# c3.net
KiCad netlist of a schematic drawn in EAGLE
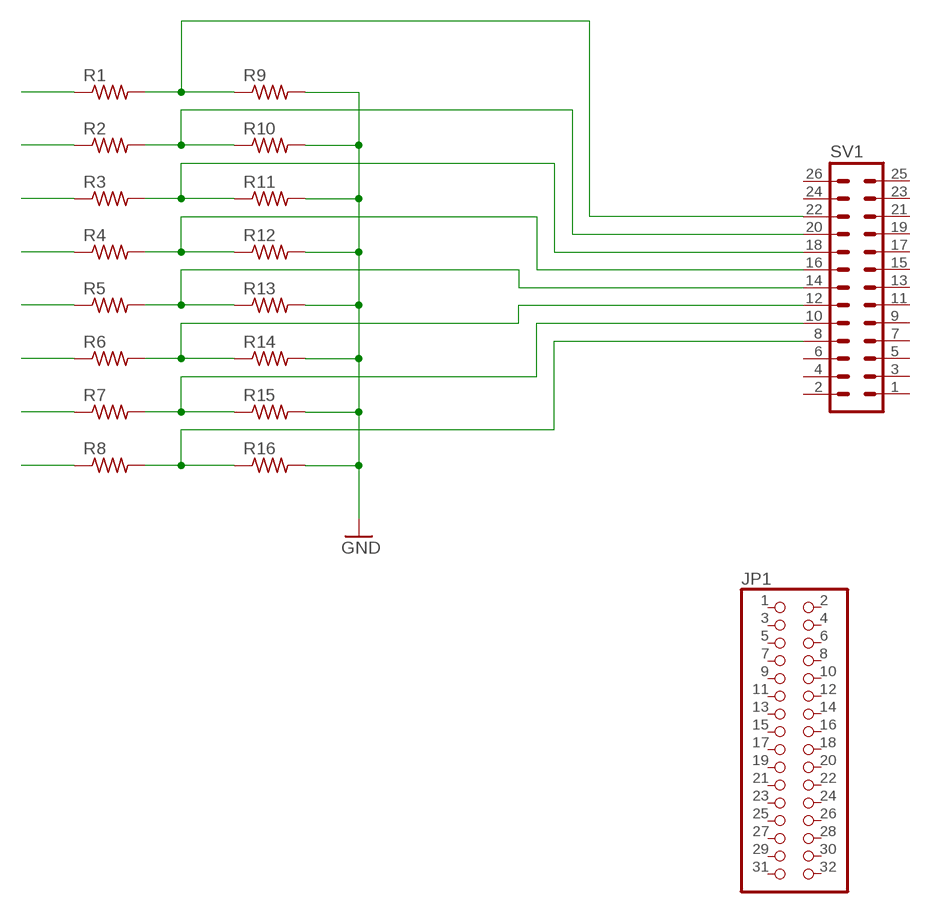
[diagram p0: schematic, sheet 1]

(export (version "E")
  (design (tool "Eeschema 10.0.6"))
  (components
    (comp (ref "JP1")
      (value "PINHD-2X16")
      (footprint "eagle-import:2X16")
      (libsource (lib "eagle-import") (part "PINHD-2X16"))
    )
    (comp (ref "R1")
      (value "R-US_0204/7")
      (footprint "eagle-import:0204_7")
      (libsource (lib "eagle-import") (part "R-US_0204/7"))
    )
    (comp (ref "R2")
      (value "R-US_0204/7")
      (footprint "eagle-import:0204_7")
      (libsource (lib "eagle-import") (part "R-US_0204/7"))
    )
    (comp (ref "R3")
      (value "R-US_0204/7")
      (footprint "eagle-import:0204_7")
      (libsource (lib "eagle-import") (part "R-US_0204/7"))
    )
    (comp (ref "R4")
      (value "R-US_0204/7")
      (footprint "eagle-import:0204_7")
      (libsource (lib "eagle-import") (part "R-US_0204/7"))
    )
    (comp (ref "R5")
      (value "R-US_0204/7")
      (footprint "eagle-import:0204_7")
      (libsource (lib "eagle-import") (part "R-US_0204/7"))
    )
    (comp (ref "R6")
      (value "R-US_0204/7")
      (footprint "eagle-import:0204_7")
      (libsource (lib "eagle-import") (part "R-US_0204/7"))
    )
    (comp (ref "R7")
      (value "R-US_0204/7")
      (footprint "eagle-import:0204_7")
      (libsource (lib "eagle-import") (part "R-US_0204/7"))
    )
    (comp (ref "R8")
      (value "R-US_0204/7")
      (footprint "eagle-import:0204_7")
      (libsource (lib "eagle-import") (part "R-US_0204/7"))
    )
    (comp (ref "R9")
      (value "R-US_0204/7")
      (footprint "eagle-import:0204_7")
      (libsource (lib "eagle-import") (part "R-US_0204/7"))
    )
    (comp (ref "R10")
      (value "R-US_0204/7")
      (footprint "eagle-import:0204_7")
      (libsource (lib "eagle-import") (part "R-US_0204/7"))
    )
    (comp (ref "R11")
      (value "R-US_0204/7")
      (footprint "eagle-import:0204_7")
      (libsource (lib "eagle-import") (part "R-US_0204/7"))
    )
    (comp (ref "R12")
      (value "R-US_0204/7")
      (footprint "eagle-import:0204_7")
      (libsource (lib "eagle-import") (part "R-US_0204/7"))
    )
    (comp (ref "R13")
      (value "R-US_0204/7")
      (footprint "eagle-import:0204_7")
      (libsource (lib "eagle-import") (part "R-US_0204/7"))
    )
    (comp (ref "R14")
      (value "R-US_0204/7")
      (footprint "eagle-import:0204_7")
      (libsource (lib "eagle-import") (part "R-US_0204/7"))
    )
    (comp (ref "R15")
      (value "R-US_0204/7")
      (footprint "eagle-import:0204_7")
      (libsource (lib "eagle-import") (part "R-US_0204/7"))
    )
    (comp (ref "R16")
      (value "R-US_0204/7")
      (footprint "eagle-import:0204_7")
      (libsource (lib "eagle-import") (part "R-US_0204/7"))
    )
    (comp (ref "SV1")
      (value "MA13-2")
      (footprint "eagle-import:MA13-2")
      (libsource (lib "eagle-import") (part "MA13-2"))
    )
  )
  (nets
    (net (code "1") (name "GND") (class "Default")
      (node (ref "R10") (pin "2") (pinfunction "2_2") (pintype "passive"))
      (node (ref "R11") (pin "2") (pinfunction "2_2") (pintype "passive"))
      (node (ref "R12") (pin "2") (pinfunction "2_2") (pintype "passive"))
      (node (ref "R13") (pin "2") (pinfunction "2_2") (pintype "passive"))
      (node (ref "R14") (pin "2") (pinfunction "2_2") (pintype "passive"))
      (node (ref "R15") (pin "2") (pinfunction "2_2") (pintype "passive"))
      (node (ref "R16") (pin "2") (pinfunction "2_2") (pintype "passive"))
      (node (ref "R9") (pin "2") (pinfunction "2_2") (pintype "passive"))
    )
    (net (code "2") (name "Net-(R1-Pad2)") (class "Default")
      (node (ref "R1") (pin "2") (pinfunction "2_2") (pintype "passive"))
      (node (ref "R9") (pin "1") (pinfunction "1_1") (pintype "passive"))
      (node (ref "SV1") (pin "22") (pinfunction "22_22") (pintype "passive"))
    )
    (net (code "3") (name "Net-(R10-Pad1)") (class "Default")
      (node (ref "R10") (pin "1") (pinfunction "1_1") (pintype "passive"))
      (node (ref "R2") (pin "2") (pinfunction "2_2") (pintype "passive"))
      (node (ref "SV1") (pin "20") (pinfunction "20_20") (pintype "passive"))
    )
    (net (code "4") (name "Net-(R11-Pad1)") (class "Default")
      (node (ref "R11") (pin "1") (pinfunction "1_1") (pintype "passive"))
      (node (ref "R3") (pin "2") (pinfunction "2_2") (pintype "passive"))
      (node (ref "SV1") (pin "18") (pinfunction "18_18") (pintype "passive"))
    )
    (net (code "5") (name "Net-(R12-Pad1)") (class "Default")
      (node (ref "R12") (pin "1") (pinfunction "1_1") (pintype "passive"))
      (node (ref "R4") (pin "2") (pinfunction "2_2") (pintype "passive"))
      (node (ref "SV1") (pin "16") (pinfunction "16_16") (pintype "passive"))
    )
    (net (code "6") (name "Net-(R13-Pad1)") (class "Default")
      (node (ref "R13") (pin "1") (pinfunction "1_1") (pintype "passive"))
      (node (ref "R5") (pin "2") (pinfunction "2_2") (pintype "passive"))
      (node (ref "SV1") (pin "14") (pinfunction "14_14") (pintype "passive"))
    )
    (net (code "7") (name "Net-(R14-Pad1)") (class "Default")
      (node (ref "R14") (pin "1") (pinfunction "1_1") (pintype "passive"))
      (node (ref "R6") (pin "2") (pinfunction "2_2") (pintype "passive"))
      (node (ref "SV1") (pin "12") (pinfunction "12_12") (pintype "passive"))
    )
    (net (code "8") (name "Net-(R15-Pad1)") (class "Default")
      (node (ref "R15") (pin "1") (pinfunction "1_1") (pintype "passive"))
      (node (ref "R7") (pin "2") (pinfunction "2_2") (pintype "passive"))
      (node (ref "SV1") (pin "10") (pinfunction "10_10") (pintype "passive"))
    )
    (net (code "9") (name "Net-(R16-Pad1)") (class "Default")
      (node (ref "R16") (pin "1") (pinfunction "1_1") (pintype "passive"))
      (node (ref "R8") (pin "2") (pinfunction "2_2") (pintype "passive"))
      (node (ref "SV1") (pin "8") (pinfunction "8_8") (pintype "passive"))
    )
    (net (code "10") (name "unconnected-(JP1-Pad1)") (class "Default")
      (node (ref "JP1") (pin "1") (pinfunction "1_1") (pintype "passive"))
    )
    (net (code "11") (name "unconnected-(JP1-Pad2)") (class "Default")
      (node (ref "JP1") (pin "2") (pinfunction "2_2") (pintype "passive"))
    )
    (net (code "12") (name "unconnected-(JP1-Pad3)") (class "Default")
      (node (ref "JP1") (pin "3") (pinfunction "3_3") (pintype "passive"))
    )
    (net (code "13") (name "unconnected-(JP1-Pad4)") (class "Default")
      (node (ref "JP1") (pin "4") (pinfunction "4_4") (pintype "passive"))
    )
    (net (code "14") (name "unconnected-(JP1-Pad5)") (class "Default")
      (node (ref "JP1") (pin "5") (pinfunction "5_5") (pintype "passive"))
    )
    (net (code "15") (name "unconnected-(JP1-Pad6)") (class "Default")
      (node (ref "JP1") (pin "6") (pinfunction "6_6") (pintype "passive"))
    )
    (net (code "16") (name "unconnected-(JP1-Pad7)") (class "Default")
      (node (ref "JP1") (pin "7") (pinfunction "7_7") (pintype "passive"))
    )
    (net (code "17") (name "unconnected-(JP1-Pad8)") (class "Default")
      (node (ref "JP1") (pin "8") (pinfunction "8_8") (pintype "passive"))
    )
    (net (code "18") (name "unconnected-(JP1-Pad9)") (class "Default")
      (node (ref "JP1") (pin "9") (pinfunction "9_9") (pintype "passive"))
    )
    (net (code "19") (name "unconnected-(JP1-Pad10)") (class "Default")
      (node (ref "JP1") (pin "10") (pinfunction "10_10") (pintype "passive"))
    )
    (net (code "20") (name "unconnected-(JP1-Pad11)") (class "Default")
      (node (ref "JP1") (pin "11") (pinfunction "11_11") (pintype "passive"))
    )
    (net (code "21") (name "unconnected-(JP1-Pad12)") (class "Default")
      (node (ref "JP1") (pin "12") (pinfunction "12_12") (pintype "passive"))
    )
    (net (code "22") (name "unconnected-(JP1-Pad13)") (class "Default")
      (node (ref "JP1") (pin "13") (pinfunction "13_13") (pintype "passive"))
    )
    (net (code "23") (name "unconnected-(JP1-Pad14)") (class "Default")
      (node (ref "JP1") (pin "14") (pinfunction "14_14") (pintype "passive"))
    )
    (net (code "24") (name "unconnected-(JP1-Pad15)") (class "Default")
      (node (ref "JP1") (pin "15") (pinfunction "15_15") (pintype "passive"))
    )
    (net (code "25") (name "unconnected-(JP1-Pad16)") (class "Default")
      (node (ref "JP1") (pin "16") (pinfunction "16_16") (pintype "passive"))
    )
    (net (code "26") (name "unconnected-(JP1-Pad17)") (class "Default")
      (node (ref "JP1") (pin "17") (pinfunction "17_17") (pintype "passive"))
    )
    (net (code "27") (name "unconnected-(JP1-Pad18)") (class "Default")
      (node (ref "JP1") (pin "18") (pinfunction "18_18") (pintype "passive"))
    )
    (net (code "28") (name "unconnected-(JP1-Pad19)") (class "Default")
      (node (ref "JP1") (pin "19") (pinfunction "19_19") (pintype "passive"))
    )
    (net (code "29") (name "unconnected-(JP1-Pad20)") (class "Default")
      (node (ref "JP1") (pin "20") (pinfunction "20_20") (pintype "passive"))
    )
    (net (code "30") (name "unconnected-(JP1-Pad21)") (class "Default")
      (node (ref "JP1") (pin "21") (pinfunction "21_21") (pintype "passive"))
    )
    (net (code "31") (name "unconnected-(JP1-Pad22)") (class "Default")
      (node (ref "JP1") (pin "22") (pinfunction "22_22") (pintype "passive"))
    )
    (net (code "32") (name "unconnected-(JP1-Pad23)") (class "Default")
      (node (ref "JP1") (pin "23") (pinfunction "23_23") (pintype "passive"))
    )
    (net (code "33") (name "unconnected-(JP1-Pad24)") (class "Default")
      (node (ref "JP1") (pin "24") (pinfunction "24_24") (pintype "passive"))
    )
    (net (code "34") (name "unconnected-(JP1-Pad25)") (class "Default")
      (node (ref "JP1") (pin "25") (pinfunction "25_25") (pintype "passive"))
    )
    (net (code "35") (name "unconnected-(JP1-Pad26)") (class "Default")
      (node (ref "JP1") (pin "26") (pinfunction "26_26") (pintype "passive"))
    )
    (net (code "36") (name "unconnected-(JP1-Pad27)") (class "Default")
      (node (ref "JP1") (pin "27") (pinfunction "27_27") (pintype "passive"))
    )
    (net (code "37") (name "unconnected-(JP1-Pad28)") (class "Default")
      (node (ref "JP1") (pin "28") (pinfunction "28_28") (pintype "passive"))
    )
    (net (code "38") (name "unconnected-(JP1-Pad29)") (class "Default")
      (node (ref "JP1") (pin "29") (pinfunction "29_29") (pintype "passive"))
    )
    (net (code "39") (name "unconnected-(JP1-Pad30)") (class "Default")
      (node (ref "JP1") (pin "30") (pinfunction "30_30") (pintype "passive"))
    )
    (net (code "40") (name "unconnected-(JP1-Pad31)") (class "Default")
      (node (ref "JP1") (pin "31") (pinfunction "31_31") (pintype "passive"))
    )
    (net (code "41") (name "unconnected-(JP1-Pad32)") (class "Default")
      (node (ref "JP1") (pin "32") (pinfunction "32_32") (pintype "passive"))
    )
    (net (code "42") (name "unconnected-(R1-Pad1)") (class "Default")
      (node (ref "R1") (pin "1") (pinfunction "1_1") (pintype "passive"))
    )
    (net (code "43") (name "unconnected-(R2-Pad1)") (class "Default")
      (node (ref "R2") (pin "1") (pinfunction "1_1") (pintype "passive"))
    )
    (net (code "44") (name "unconnected-(R3-Pad1)") (class "Default")
      (node (ref "R3") (pin "1") (pinfunction "1_1") (pintype "passive"))
    )
    (net (code "45") (name "unconnected-(R4-Pad1)") (class "Default")
      (node (ref "R4") (pin "1") (pinfunction "1_1") (pintype "passive"))
    )
    (net (code "46") (name "unconnected-(R5-Pad1)") (class "Default")
      (node (ref "R5") (pin "1") (pinfunction "1_1") (pintype "passive"))
    )
    (net (code "47") (name "unconnected-(R6-Pad1)") (class "Default")
      (node (ref "R6") (pin "1") (pinfunction "1_1") (pintype "passive"))
    )
    (net (code "48") (name "unconnected-(R7-Pad1)") (class "Default")
      (node (ref "R7") (pin "1") (pinfunction "1_1") (pintype "passive"))
    )
    (net (code "49") (name "unconnected-(R8-Pad1)") (class "Default")
      (node (ref "R8") (pin "1") (pinfunction "1_1") (pintype "passive"))
    )
    (net (code "50") (name "unconnected-(SV1-Pad1)") (class "Default")
      (node (ref "SV1") (pin "1") (pinfunction "1_1") (pintype "passive"))
    )
    (net (code "51") (name "unconnected-(SV1-Pad2)") (class "Default")
      (node (ref "SV1") (pin "2") (pinfunction "2_2") (pintype "passive"))
    )
    (net (code "52") (name "unconnected-(SV1-Pad3)") (class "Default")
      (node (ref "SV1") (pin "3") (pinfunction "3_3") (pintype "passive"))
    )
    (net (code "53") (name "unconnected-(SV1-Pad4)") (class "Default")
      (node (ref "SV1") (pin "4") (pinfunction "4_4") (pintype "passive"))
    )
    (net (code "54") (name "unconnected-(SV1-Pad5)") (class "Default")
      (node (ref "SV1") (pin "5") (pinfunction "5_5") (pintype "passive"))
    )
    (net (code "55") (name "unconnected-(SV1-Pad6)") (class "Default")
      (node (ref "SV1") (pin "6") (pinfunction "6_6") (pintype "passive"))
    )
    (net (code "56") (name "unconnected-(SV1-Pad7)") (class "Default")
      (node (ref "SV1") (pin "7") (pinfunction "7_7") (pintype "passive"))
    )
    (net (code "57") (name "unconnected-(SV1-Pad9)") (class "Default")
      (node (ref "SV1") (pin "9") (pinfunction "9_9") (pintype "passive"))
    )
    (net (code "58") (name "unconnected-(SV1-Pad11)") (class "Default")
      (node (ref "SV1") (pin "11") (pinfunction "11_11") (pintype "passive"))
    )
    (net (code "59") (name "unconnected-(SV1-Pad13)") (class "Default")
      (node (ref "SV1") (pin "13") (pinfunction "13_13") (pintype "passive"))
    )
    (net (code "60") (name "unconnected-(SV1-Pad15)") (class "Default")
      (node (ref "SV1") (pin "15") (pinfunction "15_15") (pintype "passive"))
    )
    (net (code "61") (name "unconnected-(SV1-Pad17)") (class "Default")
      (node (ref "SV1") (pin "17") (pinfunction "17_17") (pintype "passive"))
    )
    (net (code "62") (name "unconnected-(SV1-Pad19)") (class "Default")
      (node (ref "SV1") (pin "19") (pinfunction "19_19") (pintype "passive"))
    )
    (net (code "63") (name "unconnected-(SV1-Pad21)") (class "Default")
      (node (ref "SV1") (pin "21") (pinfunction "21_21") (pintype "passive"))
    )
    (net (code "64") (name "unconnected-(SV1-Pad23)") (class "Default")
      (node (ref "SV1") (pin "23") (pinfunction "23_23") (pintype "passive"))
    )
    (net (code "65") (name "unconnected-(SV1-Pad24)") (class "Default")
      (node (ref "SV1") (pin "24") (pinfunction "24_24") (pintype "passive"))
    )
    (net (code "66") (name "unconnected-(SV1-Pad25)") (class "Default")
      (node (ref "SV1") (pin "25") (pinfunction "25_25") (pintype "passive"))
    )
    (net (code "67") (name "unconnected-(SV1-Pad26)") (class "Default")
      (node (ref "SV1") (pin "26") (pinfunction "26_26") (pintype "passive"))
    )
  )
)
